# p2s.net
KiCad netlist of a schematic drawn in EAGLE
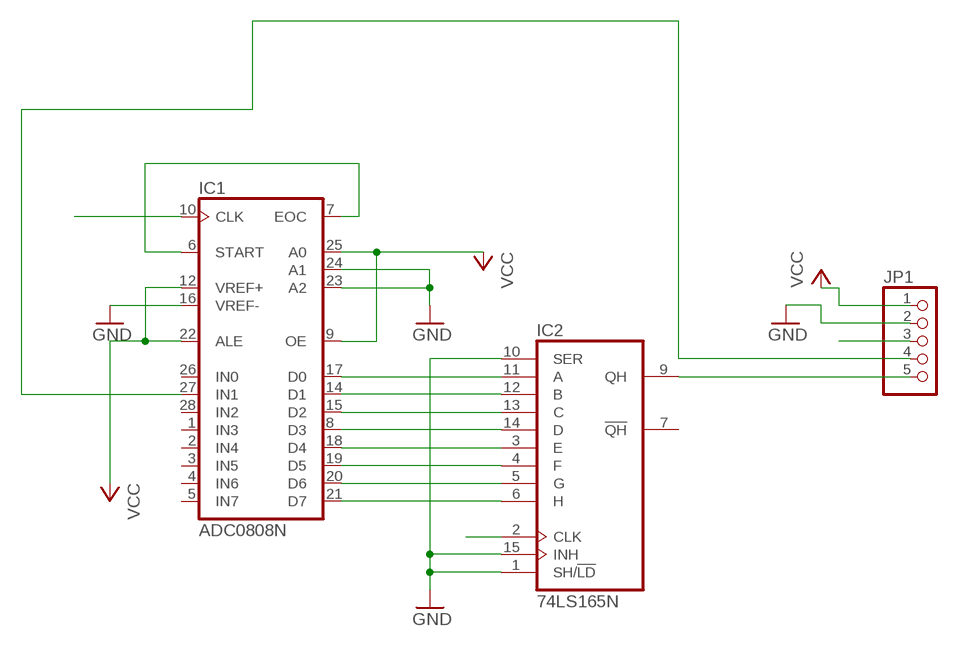
[diagram p0: schematic, sheet 1]

(export (version "E")
  (design (tool "Eeschema 10.0.6"))
  (components
    (comp (ref "IC1")
      (value "ADC0808N")
      (footprint "eagle-import:DIL28-6")
      (libsource (lib "eagle-import") (part "ADC0808N"))
    )
    (comp (ref "IC2")
      (value "74LS165N")
      (footprint "eagle-import:DIL16")
      (libsource (lib "eagle-import") (part "74165NLS"))
    )
    (comp (ref "JP1")
      (value "PINHD-1X5")
      (footprint "eagle-import:1X05")
      (libsource (lib "eagle-import") (part "PINHD-1X5"))
    )
  )
  (nets
    (net (code "1") (name "/CLK") (class "Default")
      (node (ref "IC1") (pin "10") (pinfunction "CLK_10") (pintype "input"))
      (node (ref "IC2") (pin "2") (pinfunction "CLK_2") (pintype "input"))
      (node (ref "JP1") (pin "3") (pinfunction "3_3") (pintype "passive"))
    )
    (net (code "2") (name "GND") (class "Default")
      (node (ref "IC1") (pin "16") (pinfunction "VREF-_16") (pintype "input"))
      (node (ref "IC1") (pin "23") (pinfunction "A2_23") (pintype "input"))
      (node (ref "IC1") (pin "24") (pinfunction "A1_24") (pintype "input"))
      (node (ref "IC2") (pin "1") (pinfunction "SH/~{LD}_1") (pintype "input"))
      (node (ref "IC2") (pin "10") (pinfunction "SER_10") (pintype "input"))
      (node (ref "IC2") (pin "15") (pinfunction "INH_15") (pintype "input"))
      (node (ref "JP1") (pin "2") (pinfunction "2_2") (pintype "passive"))
    )
    (net (code "3") (name "Net-(IC1A-D0)") (class "Default")
      (node (ref "IC1") (pin "17") (pinfunction "D0_17") (pintype "tri_state"))
      (node (ref "IC2") (pin "11") (pinfunction "A_11") (pintype "input"))
    )
    (net (code "4") (name "Net-(IC1A-D1)") (class "Default")
      (node (ref "IC1") (pin "14") (pinfunction "D1_14") (pintype "tri_state"))
      (node (ref "IC2") (pin "12") (pinfunction "B_12") (pintype "input"))
    )
    (net (code "5") (name "Net-(IC1A-D2)") (class "Default")
      (node (ref "IC1") (pin "15") (pinfunction "D2_15") (pintype "tri_state"))
      (node (ref "IC2") (pin "13") (pinfunction "C_13") (pintype "input"))
    )
    (net (code "6") (name "Net-(IC1A-D3)") (class "Default")
      (node (ref "IC1") (pin "8") (pinfunction "D3_8") (pintype "tri_state"))
      (node (ref "IC2") (pin "14") (pinfunction "D_14") (pintype "input"))
    )
    (net (code "7") (name "Net-(IC1A-D4)") (class "Default")
      (node (ref "IC1") (pin "18") (pinfunction "D4_18") (pintype "tri_state"))
      (node (ref "IC2") (pin "3") (pinfunction "E_3") (pintype "input"))
    )
    (net (code "8") (name "Net-(IC1A-D5)") (class "Default")
      (node (ref "IC1") (pin "19") (pinfunction "D5_19") (pintype "tri_state"))
      (node (ref "IC2") (pin "4") (pinfunction "F_4") (pintype "input"))
    )
    (net (code "9") (name "Net-(IC1A-D6)") (class "Default")
      (node (ref "IC1") (pin "20") (pinfunction "D6_20") (pintype "tri_state"))
      (node (ref "IC2") (pin "5") (pinfunction "G_5") (pintype "input"))
    )
    (net (code "10") (name "Net-(IC1A-D7)") (class "Default")
      (node (ref "IC1") (pin "21") (pinfunction "D7_21") (pintype "tri_state"))
      (node (ref "IC2") (pin "6") (pinfunction "H_6") (pintype "input"))
    )
    (net (code "11") (name "Net-(IC1A-EOC)") (class "Default")
      (node (ref "IC1") (pin "6") (pinfunction "START_6") (pintype "input"))
      (node (ref "IC1") (pin "7") (pinfunction "EOC_7") (pintype "output"))
    )
    (net (code "12") (name "Net-(IC1A-IN1)") (class "Default")
      (node (ref "IC1") (pin "27") (pinfunction "IN1_27") (pintype "input"))
      (node (ref "JP1") (pin "4") (pinfunction "4_4") (pintype "passive"))
    )
    (net (code "13") (name "Net-(IC2A-QH)") (class "Default")
      (node (ref "IC2") (pin "9") (pinfunction "QH_9") (pintype "output"))
      (node (ref "JP1") (pin "5") (pinfunction "5_5") (pintype "passive"))
    )
    (net (code "14") (name "VCC") (class "Default")
      (node (ref "IC1") (pin "12") (pinfunction "VREF+_12") (pintype "input"))
      (node (ref "IC1") (pin "22") (pinfunction "ALE_22") (pintype "input"))
      (node (ref "IC1") (pin "25") (pinfunction "A0_25") (pintype "input"))
      (node (ref "IC1") (pin "9") (pinfunction "OE_9") (pintype "input"))
      (node (ref "JP1") (pin "1") (pinfunction "1_1") (pintype "passive"))
    )
    (net (code "15") (name "unconnected-(IC1A-IN0-Pad26)") (class "Default")
      (node (ref "IC1") (pin "26") (pinfunction "IN0_26") (pintype "input"))
    )
    (net (code "16") (name "unconnected-(IC1A-IN2-Pad28)") (class "Default")
      (node (ref "IC1") (pin "28") (pinfunction "IN2_28") (pintype "input"))
    )
    (net (code "17") (name "unconnected-(IC1A-IN3-Pad1)") (class "Default")
      (node (ref "IC1") (pin "1") (pinfunction "IN3_1") (pintype "input"))
    )
    (net (code "18") (name "unconnected-(IC1A-IN4-Pad2)") (class "Default")
      (node (ref "IC1") (pin "2") (pinfunction "IN4_2") (pintype "input"))
    )
    (net (code "19") (name "unconnected-(IC1A-IN5-Pad3)") (class "Default")
      (node (ref "IC1") (pin "3") (pinfunction "IN5_3") (pintype "input"))
    )
    (net (code "20") (name "unconnected-(IC1A-IN6-Pad4)") (class "Default")
      (node (ref "IC1") (pin "4") (pinfunction "IN6_4") (pintype "input"))
    )
    (net (code "21") (name "unconnected-(IC1A-IN7-Pad5)") (class "Default")
      (node (ref "IC1") (pin "5") (pinfunction "IN7_5") (pintype "input"))
    )
    (net (code "22") (name "unconnected-(IC2A-~{QH}-Pad7)") (class "Default")
      (node (ref "IC2") (pin "7") (pinfunction "~{QH}_7") (pintype "output"))
    )
  )
)
